# SCH_Active-P1-DSMR-Switch_2025-04-20.net
KiCad netlist of a schematic drawn in EasyEDA
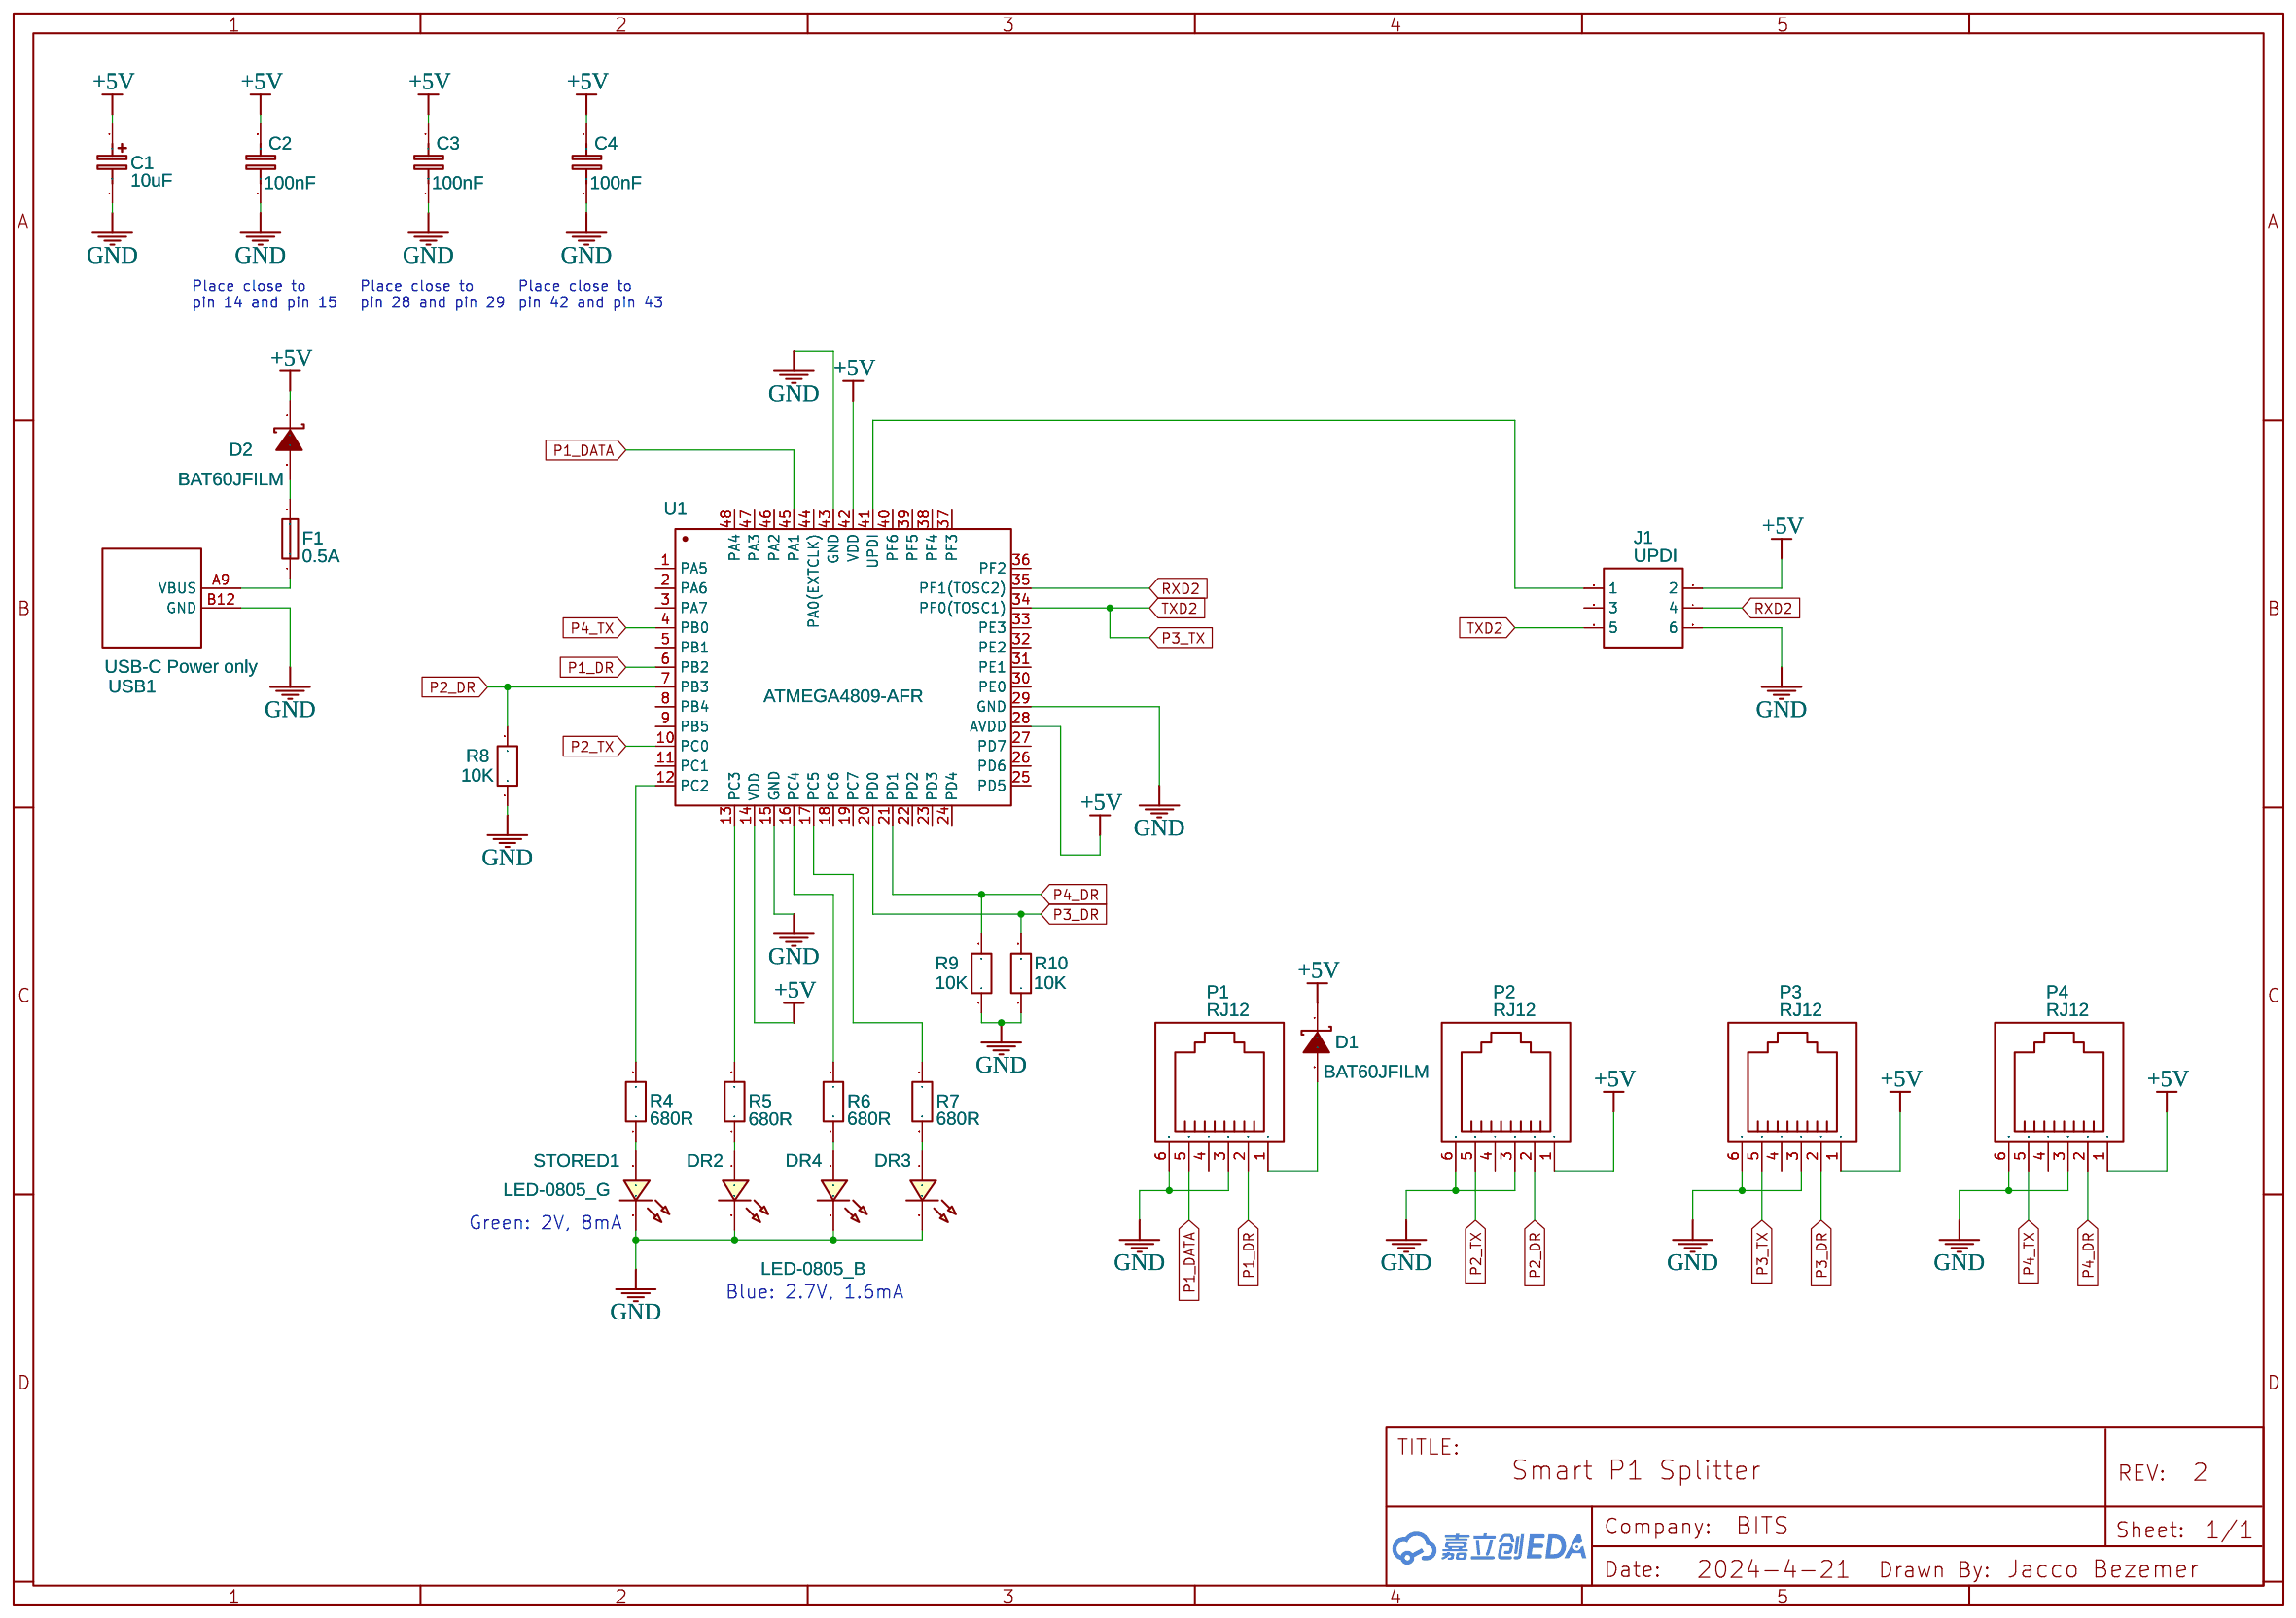
[diagram p0: schematic sheet]

(export (version "E")
  (design (tool "Eeschema 10.0.6"))
  (components
    (comp (ref "C1") (value "10uF") (libsource (lib "") (part "CE_SMD_D4.0×H5.5_EU")))
    (comp (ref "C2") (value "100nF") (libsource (lib "") (part "C_0805_EU_1")))
    (comp (ref "C3") (value "100nF") (libsource (lib "") (part "C_0805_EU")))
    (comp (ref "C4") (value "100nF") (libsource (lib "") (part "C_0805_EU")))
    (comp (ref "D1")
      (value "BAT60JFILM")
      (fields (field (name "Manufacturer") "ST(意法半导体)"))
      (libsource (lib "") (part "BAT60JFILM"))
    )
    (comp (ref "D2")
      (value "BAT60JFILM")
      (fields (field (name "Manufacturer") "ST(意法半导体)"))
      (libsource (lib "") (part "BAT60JFILM"))
    )
    (comp (ref "DR2")
      (value "LED-0805_B")
      (fields (field (name "Manufacturer Part") "D-B080508B1-KS2") (field (name "Manufacturer") "方舟 ARKLED"))
      (libsource (lib "") (part "LED-0805_B"))
    )
    (comp (ref "DR3")
      (value "LED-0805_B")
      (fields (field (name "Manufacturer Part") "D-B080508B1-KS2") (field (name "Manufacturer") "方舟 ARKLED"))
      (libsource (lib "") (part "LED-0805_B"))
    )
    (comp (ref "DR4")
      (value "LED-0805_B")
      (fields (field (name "Manufacturer Part") "D-B080508B1-KS2") (field (name "Manufacturer") "方舟 ARKLED"))
      (libsource (lib "") (part "LED-0805_B"))
    )
    (comp (ref "F1")
      (value "0.5A")
      (fields (field (name "Manufacturer Part") "2.5A/32VFUSESMD0805"))
      (libsource (lib "") (part "2.5A/32VFUSESMD0805"))
    )
    (comp (ref "J1") (value "UPDI") (libsource (lib "") (part "HDR-M-2.54_2x3")))
    (comp (ref "P1") (value "RJ12") (libsource (lib "") (part "RJ12")))
    (comp (ref "P2") (value "RJ12") (libsource (lib "") (part "RJ12")))
    (comp (ref "P3") (value "RJ12") (libsource (lib "") (part "RJ12")))
    (comp (ref "P4") (value "RJ12") (libsource (lib "") (part "RJ12")))
    (comp (ref "R4") (value "680R") (libsource (lib "") (part "R_0805_EU")))
    (comp (ref "R5") (value "680R") (libsource (lib "") (part "R_0805_EU")))
    (comp (ref "R6") (value "680R") (libsource (lib "") (part "R_0805_EU_1")))
    (comp (ref "R7") (value "680R") (libsource (lib "") (part "R_0805_EU_1")))
    (comp (ref "R8") (value "10K") (libsource (lib "") (part "R_0805_EU")))
    (comp (ref "R9") (value "10K") (libsource (lib "") (part "R_0805_EU")))
    (comp (ref "R10") (value "10K") (libsource (lib "") (part "R_0805_EU")))
    (comp (ref "STORED1")
      (value "LED-0805_G")
      (fields (field (name "Manufacturer Part") "NCD0805G1") (field (name "Manufacturer") "国星光电"))
      (libsource (lib "") (part "LED-0805_G"))
    )
    (comp (ref "U1")
      (value "ATMEGA4809-AFR")
      (fields (field (name "Manufacturer") "MICROCHIP(美国微芯)"))
      (libsource (lib "") (part "ATMEGA4809-AFR"))
    )
    (comp (ref "USB1") (value "USB-C Power only") (libsource (lib "") (part "USB-C Power only")))
  )
  (nets
    (net (code "1") (name "+5V") (class "Default")
      (node (ref "C1") (pin "1") (pinfunction "1_1") (pintype "unspecified"))
      (node (ref "C2") (pin "1") (pinfunction "1_1") (pintype "unspecified"))
      (node (ref "C3") (pin "1") (pinfunction "1_1") (pintype "unspecified"))
      (node (ref "C4") (pin "1") (pinfunction "1_1") (pintype "unspecified"))
      (node (ref "D1") (pin "1") (pinfunction "K_1") (pintype "unspecified"))
      (node (ref "D2") (pin "1") (pinfunction "K_1") (pintype "unspecified"))
      (node (ref "J1") (pin "2") (pinfunction "2_2") (pintype "input"))
      (node (ref "P2") (pin "1") (pinfunction "1_1") (pintype "unspecified"))
      (node (ref "P3") (pin "1") (pinfunction "1_1") (pintype "unspecified"))
      (node (ref "P4") (pin "1") (pinfunction "1_1") (pintype "unspecified"))
      (node (ref "U1") (pin "14") (pinfunction "VDD_14") (pintype "unspecified"))
      (node (ref "U1") (pin "28") (pinfunction "AVDD_28") (pintype "unspecified"))
      (node (ref "U1") (pin "42") (pinfunction "VDD_42") (pintype "unspecified"))
    )
    (net (code "2") (name "GND") (class "Default")
      (node (ref "C1") (pin "2") (pinfunction "2_2") (pintype "unspecified"))
      (node (ref "C2") (pin "2") (pinfunction "2_2") (pintype "unspecified"))
      (node (ref "C3") (pin "2") (pinfunction "2_2") (pintype "unspecified"))
      (node (ref "C4") (pin "2") (pinfunction "2_2") (pintype "unspecified"))
      (node (ref "DR2") (pin "2") (pinfunction "2_2") (pintype "unspecified"))
      (node (ref "DR3") (pin "2") (pinfunction "2_2") (pintype "unspecified"))
      (node (ref "DR4") (pin "2") (pinfunction "2_2") (pintype "unspecified"))
      (node (ref "J1") (pin "6") (pinfunction "6_6") (pintype "input"))
      (node (ref "P1") (pin "3") (pinfunction "3_3") (pintype "unspecified"))
      (node (ref "P1") (pin "6") (pinfunction "6_6") (pintype "unspecified"))
      (node (ref "P2") (pin "3") (pinfunction "3_3") (pintype "unspecified"))
      (node (ref "P2") (pin "6") (pinfunction "6_6") (pintype "unspecified"))
      (node (ref "P3") (pin "3") (pinfunction "3_3") (pintype "unspecified"))
      (node (ref "P3") (pin "6") (pinfunction "6_6") (pintype "unspecified"))
      (node (ref "P4") (pin "3") (pinfunction "3_3") (pintype "unspecified"))
      (node (ref "P4") (pin "6") (pinfunction "6_6") (pintype "unspecified"))
      (node (ref "R10") (pin "1") (pinfunction "1_1") (pintype "unspecified"))
      (node (ref "R8") (pin "1") (pinfunction "1_1") (pintype "unspecified"))
      (node (ref "R9") (pin "1") (pinfunction "1_1") (pintype "unspecified"))
      (node (ref "STORED1") (pin "2") (pinfunction "2_2") (pintype "unspecified"))
      (node (ref "U1") (pin "15") (pinfunction "GND_15") (pintype "unspecified"))
      (node (ref "U1") (pin "29") (pinfunction "GND_29") (pintype "unspecified"))
      (node (ref "U1") (pin "43") (pinfunction "GND_43") (pintype "unspecified"))
      (node (ref "USB1") (pin "B12") (pinfunction "GND_B12") (pintype "unspecified"))
    )
    (net (code "3") (name "Net-(D1-A)") (class "Default")
      (node (ref "D1") (pin "2") (pinfunction "A_2") (pintype "unspecified"))
      (node (ref "P1") (pin "1") (pinfunction "1_1") (pintype "unspecified"))
    )
    (net (code "4") (name "Net-(D2-A)") (class "Default")
      (node (ref "D2") (pin "2") (pinfunction "A_2") (pintype "unspecified"))
      (node (ref "F1") (pin "2") (pinfunction "2_2") (pintype "unspecified"))
    )
    (net (code "5") (name "Net-(DR2-Pad1)") (class "Default")
      (node (ref "DR2") (pin "1") (pinfunction "1_1") (pintype "unspecified"))
      (node (ref "R5") (pin "1") (pinfunction "1_1") (pintype "unspecified"))
    )
    (net (code "6") (name "Net-(DR3-Pad1)") (class "Default")
      (node (ref "DR3") (pin "1") (pinfunction "1_1") (pintype "unspecified"))
      (node (ref "R7") (pin "2") (pinfunction "2_2") (pintype "unspecified"))
    )
    (net (code "7") (name "Net-(DR4-Pad1)") (class "Default")
      (node (ref "DR4") (pin "1") (pinfunction "1_1") (pintype "unspecified"))
      (node (ref "R6") (pin "2") (pinfunction "2_2") (pintype "unspecified"))
    )
    (net (code "8") (name "Net-(R4-Pad1)") (class "Default")
      (node (ref "R4") (pin "1") (pinfunction "1_1") (pintype "unspecified"))
      (node (ref "STORED1") (pin "1") (pinfunction "1_1") (pintype "unspecified"))
    )
    (net (code "9") (name "Net-(U1-PC2)") (class "Default")
      (node (ref "R4") (pin "2") (pinfunction "2_2") (pintype "unspecified"))
      (node (ref "U1") (pin "12") (pinfunction "PC2_12") (pintype "unspecified"))
    )
    (net (code "10") (name "Net-(U1-PC3)") (class "Default")
      (node (ref "R5") (pin "2") (pinfunction "2_2") (pintype "unspecified"))
      (node (ref "U1") (pin "13") (pinfunction "PC3_13") (pintype "unspecified"))
    )
    (net (code "11") (name "Net-(U1-PC4)") (class "Default")
      (node (ref "R6") (pin "1") (pinfunction "1_1") (pintype "unspecified"))
      (node (ref "U1") (pin "16") (pinfunction "PC4_16") (pintype "unspecified"))
    )
    (net (code "12") (name "Net-(U1-PC5)") (class "Default")
      (node (ref "R7") (pin "1") (pinfunction "1_1") (pintype "unspecified"))
      (node (ref "U1") (pin "17") (pinfunction "PC5_17") (pintype "unspecified"))
    )
    (net (code "13") (name "Net-(U1-UPDI)") (class "Default")
      (node (ref "J1") (pin "1") (pinfunction "1_1") (pintype "input"))
      (node (ref "U1") (pin "41") (pinfunction "UPDI_41") (pintype "unspecified"))
    )
    (net (code "14") (name "Net-(USB1-VBUS)") (class "Default")
      (node (ref "F1") (pin "1") (pinfunction "1_1") (pintype "unspecified"))
      (node (ref "USB1") (pin "A9") (pinfunction "VBUS_A9") (pintype "unspecified"))
    )
    (net (code "15") (name "P1_DATA") (class "Default")
      (node (ref "P1") (pin "5") (pinfunction "5_5") (pintype "unspecified"))
      (node (ref "U1") (pin "45") (pinfunction "PA1_45") (pintype "unspecified"))
    )
    (net (code "16") (name "P1_DR") (class "Default")
      (node (ref "P1") (pin "2") (pinfunction "2_2") (pintype "unspecified"))
      (node (ref "U1") (pin "6") (pinfunction "PB2_6") (pintype "unspecified"))
    )
    (net (code "17") (name "P2_DR") (class "Default")
      (node (ref "P2") (pin "2") (pinfunction "2_2") (pintype "unspecified"))
      (node (ref "R8") (pin "2") (pinfunction "2_2") (pintype "unspecified"))
      (node (ref "U1") (pin "7") (pinfunction "PB3_7") (pintype "unspecified"))
    )
    (net (code "18") (name "P2_TX") (class "Default")
      (node (ref "P2") (pin "5") (pinfunction "5_5") (pintype "unspecified"))
      (node (ref "U1") (pin "10") (pinfunction "PC0_10") (pintype "unspecified"))
    )
    (net (code "19") (name "P3_DR") (class "Default")
      (node (ref "P3") (pin "2") (pinfunction "2_2") (pintype "unspecified"))
      (node (ref "R10") (pin "2") (pinfunction "2_2") (pintype "unspecified"))
      (node (ref "U1") (pin "20") (pinfunction "PD0_20") (pintype "unspecified"))
    )
    (net (code "20") (name "P3_TX") (class "Default")
      (node (ref "J1") (pin "5") (pinfunction "5_5") (pintype "input"))
      (node (ref "P3") (pin "5") (pinfunction "5_5") (pintype "unspecified"))
      (node (ref "U1") (pin "34") (pinfunction "PF0(TOSC1)_34") (pintype "unspecified"))
    )
    (net (code "21") (name "P4_DR") (class "Default")
      (node (ref "P4") (pin "2") (pinfunction "2_2") (pintype "unspecified"))
      (node (ref "R9") (pin "2") (pinfunction "2_2") (pintype "unspecified"))
      (node (ref "U1") (pin "21") (pinfunction "PD1_21") (pintype "unspecified"))
    )
    (net (code "22") (name "P4_TX") (class "Default")
      (node (ref "P4") (pin "5") (pinfunction "5_5") (pintype "unspecified"))
      (node (ref "U1") (pin "4") (pinfunction "PB0_4") (pintype "unspecified"))
    )
    (net (code "23") (name "RXD2") (class "Default")
      (node (ref "J1") (pin "4") (pinfunction "4_4") (pintype "input"))
      (node (ref "U1") (pin "35") (pinfunction "PF1(TOSC2)_35") (pintype "unspecified"))
    )
    (net (code "24") (name "unconnected-(J1-Pad3)") (class "Default")
      (node (ref "J1") (pin "3") (pinfunction "3_3") (pintype "input"))
    )
    (net (code "25") (name "unconnected-(P1-Pad4)") (class "Default")
      (node (ref "P1") (pin "4") (pinfunction "4_4") (pintype "unspecified"))
    )
    (net (code "26") (name "unconnected-(P2-Pad4)") (class "Default")
      (node (ref "P2") (pin "4") (pinfunction "4_4") (pintype "unspecified"))
    )
    (net (code "27") (name "unconnected-(P3-Pad4)") (class "Default")
      (node (ref "P3") (pin "4") (pinfunction "4_4") (pintype "unspecified"))
    )
    (net (code "28") (name "unconnected-(P4-Pad4)") (class "Default")
      (node (ref "P4") (pin "4") (pinfunction "4_4") (pintype "unspecified"))
    )
    (net (code "29") (name "unconnected-(U1-PA0(EXTCLK)-Pad44)") (class "Default")
      (node (ref "U1") (pin "44") (pinfunction "PA0(EXTCLK)_44") (pintype "unspecified"))
    )
    (net (code "30") (name "unconnected-(U1-PA2-Pad46)") (class "Default")
      (node (ref "U1") (pin "46") (pinfunction "PA2_46") (pintype "unspecified"))
    )
    (net (code "31") (name "unconnected-(U1-PA3-Pad47)") (class "Default")
      (node (ref "U1") (pin "47") (pinfunction "PA3_47") (pintype "unspecified"))
    )
    (net (code "32") (name "unconnected-(U1-PA4-Pad48)") (class "Default")
      (node (ref "U1") (pin "48") (pinfunction "PA4_48") (pintype "unspecified"))
    )
    (net (code "33") (name "unconnected-(U1-PA5-Pad1)") (class "Default")
      (node (ref "U1") (pin "1") (pinfunction "PA5_1") (pintype "unspecified"))
    )
    (net (code "34") (name "unconnected-(U1-PA6-Pad2)") (class "Default")
      (node (ref "U1") (pin "2") (pinfunction "PA6_2") (pintype "unspecified"))
    )
    (net (code "35") (name "unconnected-(U1-PA7-Pad3)") (class "Default")
      (node (ref "U1") (pin "3") (pinfunction "PA7_3") (pintype "unspecified"))
    )
    (net (code "36") (name "unconnected-(U1-PB1-Pad5)") (class "Default")
      (node (ref "U1") (pin "5") (pinfunction "PB1_5") (pintype "unspecified"))
    )
    (net (code "37") (name "unconnected-(U1-PB4-Pad8)") (class "Default")
      (node (ref "U1") (pin "8") (pinfunction "PB4_8") (pintype "unspecified"))
    )
    (net (code "38") (name "unconnected-(U1-PB5-Pad9)") (class "Default")
      (node (ref "U1") (pin "9") (pinfunction "PB5_9") (pintype "unspecified"))
    )
    (net (code "39") (name "unconnected-(U1-PC1-Pad11)") (class "Default")
      (node (ref "U1") (pin "11") (pinfunction "PC1_11") (pintype "unspecified"))
    )
    (net (code "40") (name "unconnected-(U1-PC6-Pad18)") (class "Default")
      (node (ref "U1") (pin "18") (pinfunction "PC6_18") (pintype "unspecified"))
    )
    (net (code "41") (name "unconnected-(U1-PC7-Pad19)") (class "Default")
      (node (ref "U1") (pin "19") (pinfunction "PC7_19") (pintype "unspecified"))
    )
    (net (code "42") (name "unconnected-(U1-PD2-Pad22)") (class "Default")
      (node (ref "U1") (pin "22") (pinfunction "PD2_22") (pintype "unspecified"))
    )
    (net (code "43") (name "unconnected-(U1-PD3-Pad23)") (class "Default")
      (node (ref "U1") (pin "23") (pinfunction "PD3_23") (pintype "unspecified"))
    )
    (net (code "44") (name "unconnected-(U1-PD4-Pad24)") (class "Default")
      (node (ref "U1") (pin "24") (pinfunction "PD4_24") (pintype "unspecified"))
    )
    (net (code "45") (name "unconnected-(U1-PD5-Pad25)") (class "Default")
      (node (ref "U1") (pin "25") (pinfunction "PD5_25") (pintype "unspecified"))
    )
    (net (code "46") (name "unconnected-(U1-PD6-Pad26)") (class "Default")
      (node (ref "U1") (pin "26") (pinfunction "PD6_26") (pintype "unspecified"))
    )
    (net (code "47") (name "unconnected-(U1-PD7-Pad27)") (class "Default")
      (node (ref "U1") (pin "27") (pinfunction "PD7_27") (pintype "unspecified"))
    )
    (net (code "48") (name "unconnected-(U1-PE0-Pad30)") (class "Default")
      (node (ref "U1") (pin "30") (pinfunction "PE0_30") (pintype "unspecified"))
    )
    (net (code "49") (name "unconnected-(U1-PE1-Pad31)") (class "Default")
      (node (ref "U1") (pin "31") (pinfunction "PE1_31") (pintype "unspecified"))
    )
    (net (code "50") (name "unconnected-(U1-PE2-Pad32)") (class "Default")
      (node (ref "U1") (pin "32") (pinfunction "PE2_32") (pintype "unspecified"))
    )
    (net (code "51") (name "unconnected-(U1-PE3-Pad33)") (class "Default")
      (node (ref "U1") (pin "33") (pinfunction "PE3_33") (pintype "unspecified"))
    )
    (net (code "52") (name "unconnected-(U1-PF2-Pad36)") (class "Default")
      (node (ref "U1") (pin "36") (pinfunction "PF2_36") (pintype "unspecified"))
    )
    (net (code "53") (name "unconnected-(U1-PF3-Pad37)") (class "Default")
      (node (ref "U1") (pin "37") (pinfunction "PF3_37") (pintype "unspecified"))
    )
    (net (code "54") (name "unconnected-(U1-PF4-Pad38)") (class "Default")
      (node (ref "U1") (pin "38") (pinfunction "PF4_38") (pintype "unspecified"))
    )
    (net (code "55") (name "unconnected-(U1-PF5-Pad39)") (class "Default")
      (node (ref "U1") (pin "39") (pinfunction "PF5_39") (pintype "unspecified"))
    )
    (net (code "56") (name "unconnected-(U1-PF6-Pad40)") (class "Default")
      (node (ref "U1") (pin "40") (pinfunction "PF6_40") (pintype "unspecified"))
    )
  )
)
